# testpoint.net
KiCad netlist of a schematic drawn in Altium Designer
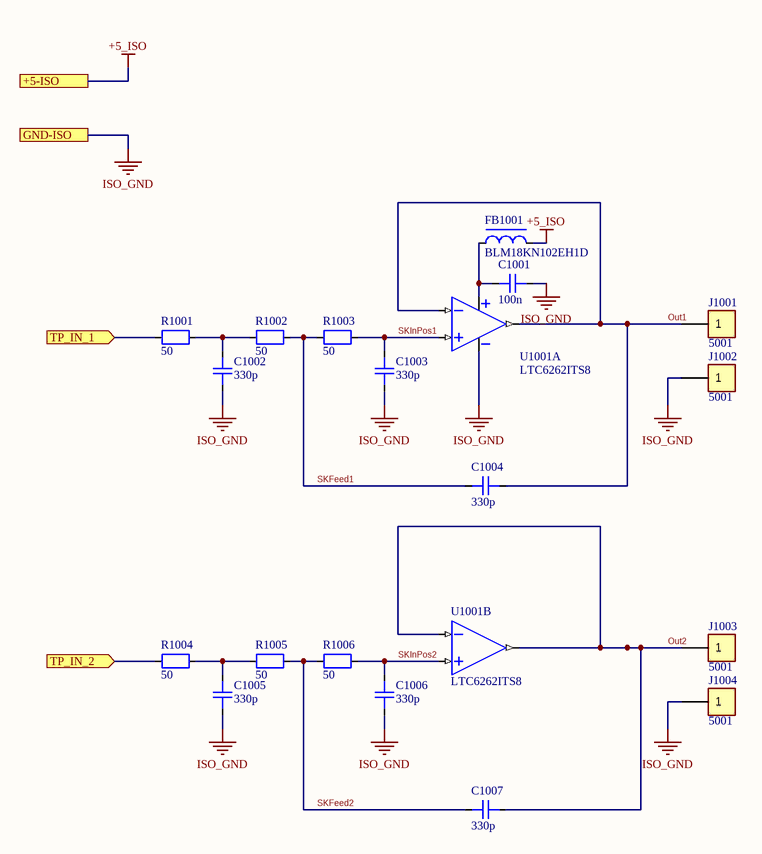
[diagram p0: testpoint.SchDoc]

(export (version "E")
  (design (tool "Eeschema 10.0.6"))
  (components
    (comp (ref "C1001")
      (value "100n")
      (footprint "CAP0603")
      (libsource (lib "schematic_library") (part "Capacitor"))
    )
    (comp (ref "C1002")
      (value "330p")
      (footprint "CAP0603")
      (libsource (lib "Integrated_Library") (part "Capacitor"))
    )
    (comp (ref "C1003")
      (value "330p")
      (footprint "CAP0603")
      (libsource (lib "Integrated_Library") (part "Capacitor"))
    )
    (comp (ref "C1004")
      (value "330p")
      (footprint "CAP0603")
      (libsource (lib "Integrated_Library") (part "Capacitor"))
    )
    (comp (ref "C1005")
      (value "330p")
      (footprint "CAP0603")
      (libsource (lib "Integrated_Library") (part "Capacitor"))
    )
    (comp (ref "C1006")
      (value "330p")
      (footprint "CAP0603")
      (libsource (lib "Integrated_Library") (part "Capacitor"))
    )
    (comp (ref "C1007")
      (value "330p")
      (footprint "CAP0603")
      (libsource (lib "Integrated_Library") (part "Capacitor"))
    )
    (comp (ref "FB1001")
      (value "BLM18KN102EH1D")
      (footprint "RES0603")
      (libsource (lib "schematic_library") (part "Ferrite Bead"))
    )
    (comp (ref "J1001")
      (value "5001")
      (footprint "FP-5001-MFG")
      (description "PC TEST POINT MINIATURE BLACK")
      (libsource (lib "schematic_library") (part "5001"))
    )
    (comp (ref "J1002")
      (value "5001")
      (footprint "FP-5001-MFG")
      (description "PC TEST POINT MINIATURE BLACK")
      (libsource (lib "schematic_library") (part "5001"))
    )
    (comp (ref "J1003")
      (value "5001")
      (footprint "FP-5001-MFG")
      (description "PC TEST POINT MINIATURE BLACK")
      (libsource (lib "schematic_library") (part "5001"))
    )
    (comp (ref "J1004")
      (value "5001")
      (footprint "FP-5001-MFG")
      (description "PC TEST POINT MINIATURE BLACK")
      (libsource (lib "schematic_library") (part "5001"))
    )
    (comp (ref "R1001")
      (value "50")
      (footprint "RES0603")
      (libsource (lib "Integrated_Library") (part "Resistor"))
    )
    (comp (ref "R1002")
      (value "50")
      (footprint "RES0603")
      (libsource (lib "Integrated_Library") (part "Resistor"))
    )
    (comp (ref "R1003")
      (value "50")
      (footprint "RES0603")
      (libsource (lib "Integrated_Library") (part "Resistor"))
    )
    (comp (ref "R1004")
      (value "50")
      (footprint "RES0603")
      (libsource (lib "Integrated_Library") (part "Resistor"))
    )
    (comp (ref "R1005")
      (value "50")
      (footprint "RES0603")
      (libsource (lib "Integrated_Library") (part "Resistor"))
    )
    (comp (ref "R1006")
      (value "50")
      (footprint "RES0603")
      (libsource (lib "Integrated_Library") (part "Resistor"))
    )
    (comp (ref "U1001")
      (value "LTC6262ITS8")
      (footprint "TSOP65P280X100-8N")
      (description "Op Amps 2x 30MHz, 240 A Pwr Eff R2R I/O Op Amps")
      (libsource (lib "schematic_library") (part "LTC6262ITS8"))
    )
  )
  (nets
    (net (code "1") (name "+5_ISO") (class "Default") (node (ref "FB1001") (pin "1") (pintype "passive")))
    (net (code "2") (name "/Out1") (class "Default")
      (node (ref "C1004") (pin "1") (pintype "passive"))
      (node (ref "J1001") (pin "1") (pinfunction "1_1") (pintype "passive"))
      (node (ref "U1001") (pin "1") (pinfunction "OUTA_1") (pintype "output"))
      (node (ref "U1001") (pin "2") (pinfunction "-INA_2") (pintype "input"))
    )
    (net (code "3") (name "/Out2") (class "Default")
      (node (ref "C1007") (pin "1") (pintype "passive"))
      (node (ref "J1003") (pin "1") (pinfunction "1_1") (pintype "passive"))
      (node (ref "U1001") (pin "6") (pinfunction "-INB_6") (pintype "input"))
      (node (ref "U1001") (pin "7") (pinfunction "OUTB_7") (pintype "output"))
    )
    (net (code "4") (name "/SKFeed1") (class "Default")
      (node (ref "C1004") (pin "2") (pintype "passive"))
      (node (ref "R1002") (pin "1") (pintype "passive"))
      (node (ref "R1003") (pin "2") (pintype "passive"))
    )
    (net (code "5") (name "/SKFeed2") (class "Default")
      (node (ref "C1007") (pin "2") (pintype "passive"))
      (node (ref "R1005") (pin "1") (pintype "passive"))
      (node (ref "R1006") (pin "2") (pintype "passive"))
    )
    (net (code "6") (name "/SKInPos1") (class "Default")
      (node (ref "C1003") (pin "1") (pintype "passive"))
      (node (ref "R1003") (pin "1") (pintype "passive"))
      (node (ref "U1001") (pin "3") (pinfunction "+INB_3") (pintype "input"))
    )
    (net (code "7") (name "/SKInPos2") (class "Default")
      (node (ref "C1006") (pin "1") (pintype "passive"))
      (node (ref "R1006") (pin "1") (pintype "passive"))
      (node (ref "U1001") (pin "5") (pinfunction "+INB_5") (pintype "input"))
    )
    (net (code "8") (name "/TP_IN_1") (class "Default") (node (ref "R1001") (pin "2") (pintype "passive")))
    (net (code "9") (name "/TP_IN_2") (class "Default") (node (ref "R1004") (pin "2") (pintype "passive")))
    (net (code "10") (name "ISO_GND") (class "Default")
      (node (ref "C1001") (pin "2") (pintype "passive"))
      (node (ref "C1002") (pin "2") (pintype "passive"))
      (node (ref "C1003") (pin "2") (pintype "passive"))
      (node (ref "C1005") (pin "2") (pintype "passive"))
      (node (ref "C1006") (pin "2") (pintype "passive"))
      (node (ref "J1002") (pin "1") (pinfunction "1_1") (pintype "passive"))
      (node (ref "J1004") (pin "1") (pinfunction "1_1") (pintype "passive"))
      (node (ref "U1001") (pin "4") (pinfunction "-V_4") (pintype "passive"))
    )
    (net (code "11") (name "Net-(C1002-Pad1)") (class "Default")
      (node (ref "C1002") (pin "1") (pintype "passive"))
      (node (ref "R1001") (pin "1") (pintype "passive"))
      (node (ref "R1002") (pin "2") (pintype "passive"))
    )
    (net (code "12") (name "Net-(C1005-Pad1)") (class "Default")
      (node (ref "C1005") (pin "1") (pintype "passive"))
      (node (ref "R1004") (pin "1") (pintype "passive"))
      (node (ref "R1005") (pin "2") (pintype "passive"))
    )
    (net (code "13") (name "Net-(U1001A-+V)") (class "Default")
      (node (ref "C1001") (pin "1") (pintype "passive"))
      (node (ref "FB1001") (pin "2") (pintype "passive"))
      (node (ref "U1001") (pin "8") (pinfunction "+V_8") (pintype "passive"))
    )
  )
)
